# ADG714_DAC_MUX.net
KiCad netlist of a schematic drawn in Altium Designer
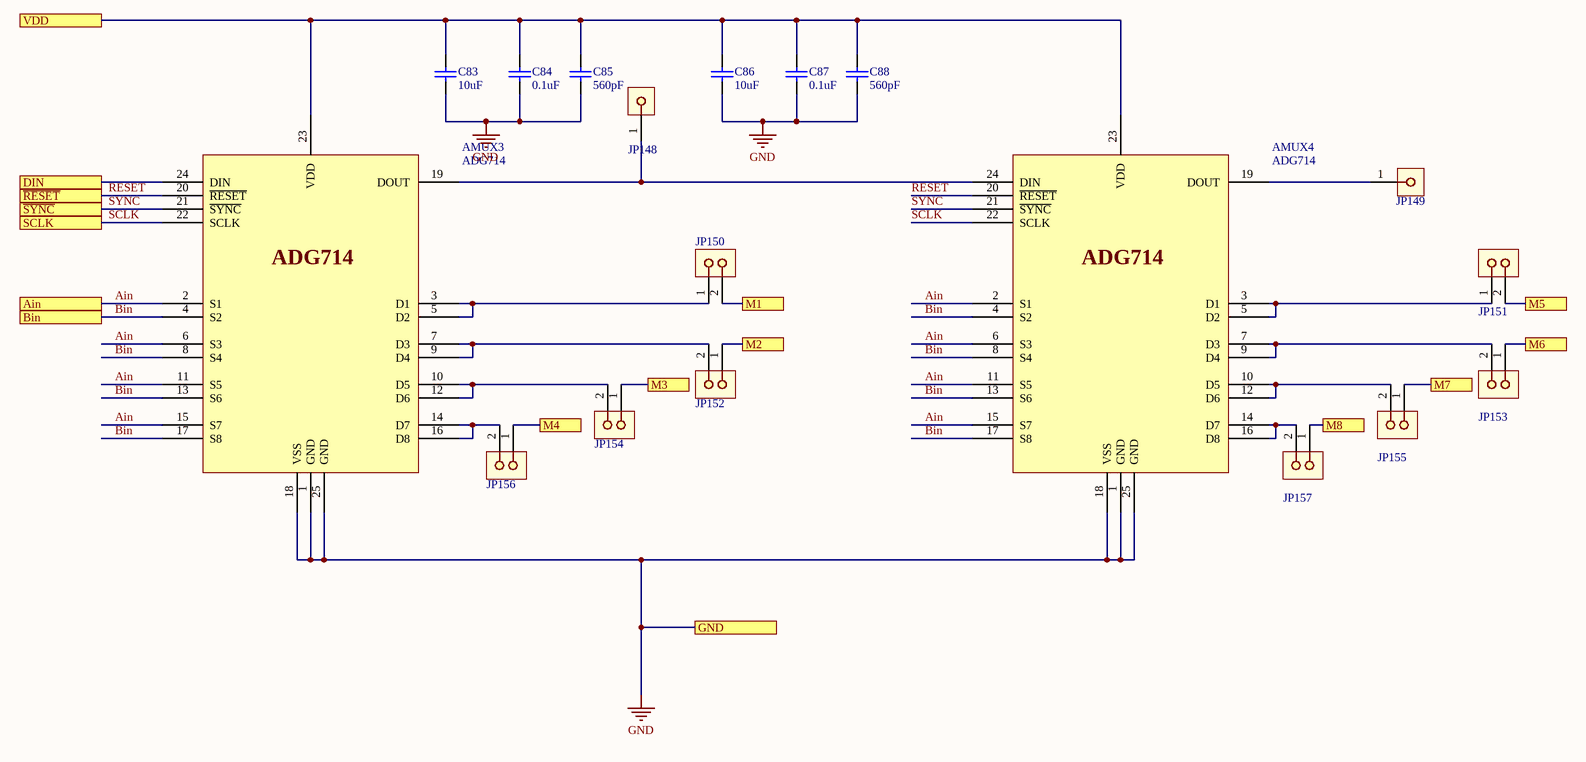
[diagram p0: ADG714_DAC_MUX.SchDoc]

(export (version "E")
  (design (tool "Eeschema 10.0.6"))
  (components
    (comp (ref "AMUX3")
      (value "ADG714")
      (footprint "ADG714BCPZ")
      (description "Analog MUX")
      (libsource (lib "Chip1_TestBoard") (part "ADG714"))
    )
    (comp (ref "AMUX4")
      (value "ADG714")
      (footprint "ADG714BCPZ")
      (description "Analog MUX")
      (libsource (lib "Chip1_TestBoard") (part "ADG714"))
    )
    (comp (ref "C83")
      (value "10uF")
      (footprint "CLS_Library:C0805")
      (description "Cap 10uF")
      (fields
        (field (name "MANUFACTURER") "Taiyo Yuden")
        (field (name "MANUFACTURER PART NUMBER") "UMK212SD103KD-T")
      )
      (libsource (lib "Chip1_TestBoard") (part "Cap 10uF"))
    )
    (comp (ref "C84")
      (value "0.1uF")
      (footprint "CLS_Library:C0805")
      (description "Cap 0.1uF")
      (fields
        (field (name "MANUFACTURER") "Taiyo Yuden")
        (field (name "MANUFACTURER PART NUMBER") "UMK212SD103KD-T")
      )
      (libsource (lib "Chip1_TestBoard") (part "Cap 0.1uF"))
    )
    (comp (ref "C85")
      (value "560pF")
      (footprint "CLS_Library:C0805")
      (description "Cap 560pF")
      (fields
        (field (name "MANUFACTURER") "Taiyo Yuden")
        (field (name "MANUFACTURER PART NUMBER") "UMK212SD103KD-T")
      )
      (libsource (lib "Chip1_TestBoard") (part "Cap 560pF"))
    )
    (comp (ref "C86")
      (value "10uF")
      (footprint "CLS_Library:C0805")
      (description "Cap 10uF")
      (fields
        (field (name "MANUFACTURER") "Taiyo Yuden")
        (field (name "MANUFACTURER PART NUMBER") "UMK212SD103KD-T")
      )
      (libsource (lib "Chip1_TestBoard") (part "Cap 10uF"))
    )
    (comp (ref "C87")
      (value "0.1uF")
      (footprint "CLS_Library:C0805")
      (description "Cap 0.1uF")
      (fields
        (field (name "MANUFACTURER") "Taiyo Yuden")
        (field (name "MANUFACTURER PART NUMBER") "UMK212SD103KD-T")
      )
      (libsource (lib "Chip1_TestBoard") (part "Cap 0.1uF"))
    )
    (comp (ref "C88")
      (value "560pF")
      (footprint "CLS_Library:C0805")
      (description "Cap 560pF")
      (fields
        (field (name "MANUFACTURER") "Taiyo Yuden")
        (field (name "MANUFACTURER PART NUMBER") "UMK212SD103KD-T")
      )
      (libsource (lib "Chip1_TestBoard") (part "Cap 560pF"))
    )
    (comp (ref "JP148")
      (value "01x01")
      (footprint "01x01_0_0.1in_th_straight_b_nom")
      (description "01X01 generic terminal connector")
      (libsource (lib "") (part "01x01_1"))
    )
    (comp (ref "JP149")
      (value "01x01")
      (footprint "01x01_0_0.1in_th_straight_b_nom")
      (description "01X01 generic terminal connector")
      (libsource (lib "Chip1_TestBoard") (part "01x01"))
    )
    (comp (ref "JP150")
      (value "01x02")
      (footprint "01x02_0.1in_th_straight_b_nom")
      (description "01X02 generic terminal connector")
      (libsource (lib "Chip1_TestBoard") (part "01x02"))
    )
    (comp (ref "JP151")
      (value "01x02")
      (footprint "01x02_0.1in_th_straight_b_nom")
      (description "01X02 generic terminal connector")
      (libsource (lib "Chip1_TestBoard") (part "01x02"))
    )
    (comp (ref "JP152")
      (value "01x02")
      (footprint "01x02_0.1in_th_straight_b_nom")
      (description "01X02 generic terminal connector")
      (libsource (lib "") (part "01x02_1"))
    )
    (comp (ref "JP153")
      (value "01x02")
      (footprint "01x02_0.1in_th_straight_b_nom")
      (description "01X02 generic terminal connector")
      (libsource (lib "") (part "01x02_1"))
    )
    (comp (ref "JP154")
      (value "01x02")
      (footprint "01x02_0.1in_th_straight_b_nom")
      (description "01X02 generic terminal connector")
      (libsource (lib "") (part "01x02_1"))
    )
    (comp (ref "JP155")
      (value "01x02")
      (footprint "01x02_0.1in_th_straight_b_nom")
      (description "01X02 generic terminal connector")
      (libsource (lib "") (part "01x02_1"))
    )
    (comp (ref "JP156")
      (value "01x02")
      (footprint "01x02_0.1in_th_straight_b_nom")
      (description "01X02 generic terminal connector")
      (libsource (lib "") (part "01x02_1"))
    )
    (comp (ref "JP157")
      (value "01x02")
      (footprint "01x02_0.1in_th_straight_b_nom")
      (description "01X02 generic terminal connector")
      (libsource (lib "") (part "01x02_1"))
    )
  )
  (nets
    (net (code "1") (name "/Ain") (class "Default")
      (node (ref "AMUX3") (pin "11") (pinfunction "S5_11") (pintype "passive"))
      (node (ref "AMUX3") (pin "15") (pinfunction "S7_15") (pintype "passive"))
      (node (ref "AMUX3") (pin "2") (pinfunction "S1_2") (pintype "passive"))
      (node (ref "AMUX3") (pin "6") (pinfunction "S3_6") (pintype "passive"))
      (node (ref "AMUX4") (pin "11") (pinfunction "S5_11") (pintype "passive"))
      (node (ref "AMUX4") (pin "15") (pinfunction "S7_15") (pintype "passive"))
      (node (ref "AMUX4") (pin "2") (pinfunction "S1_2") (pintype "passive"))
      (node (ref "AMUX4") (pin "6") (pinfunction "S3_6") (pintype "passive"))
    )
    (net (code "2") (name "/Bin") (class "Default")
      (node (ref "AMUX3") (pin "13") (pinfunction "S6_13") (pintype "passive"))
      (node (ref "AMUX3") (pin "17") (pinfunction "S8_17") (pintype "passive"))
      (node (ref "AMUX3") (pin "4") (pinfunction "S2_4") (pintype "passive"))
      (node (ref "AMUX3") (pin "8") (pinfunction "S4_8") (pintype "passive"))
      (node (ref "AMUX4") (pin "13") (pinfunction "S6_13") (pintype "passive"))
      (node (ref "AMUX4") (pin "17") (pinfunction "S8_17") (pintype "passive"))
      (node (ref "AMUX4") (pin "4") (pinfunction "S2_4") (pintype "passive"))
      (node (ref "AMUX4") (pin "8") (pinfunction "S4_8") (pintype "passive"))
    )
    (net (code "3") (name "/DIN") (class "Default")
      (node (ref "AMUX3") (pin "24") (pinfunction "DIN_24") (pintype "passive"))
    )
    (net (code "4") (name "/M1") (class "Default")
      (node (ref "JP150") (pin "2") (pinfunction "2_2") (pintype "passive"))
    )
    (net (code "5") (name "/M2") (class "Default")
      (node (ref "JP152") (pin "1") (pinfunction "1_1") (pintype "passive"))
    )
    (net (code "6") (name "/M3") (class "Default")
      (node (ref "JP154") (pin "1") (pinfunction "1_1") (pintype "passive"))
    )
    (net (code "7") (name "/M4") (class "Default")
      (node (ref "JP156") (pin "1") (pinfunction "1_1") (pintype "passive"))
    )
    (net (code "8") (name "/M5") (class "Default")
      (node (ref "JP151") (pin "2") (pinfunction "2_2") (pintype "passive"))
    )
    (net (code "9") (name "/M6") (class "Default")
      (node (ref "JP153") (pin "1") (pinfunction "1_1") (pintype "passive"))
    )
    (net (code "10") (name "/M7") (class "Default")
      (node (ref "JP155") (pin "1") (pinfunction "1_1") (pintype "passive"))
    )
    (net (code "11") (name "/M8") (class "Default")
      (node (ref "JP157") (pin "1") (pinfunction "1_1") (pintype "passive"))
    )
    (net (code "12") (name "/SCLK") (class "Default")
      (node (ref "AMUX3") (pin "22") (pinfunction "SCLK_22") (pintype "passive"))
      (node (ref "AMUX4") (pin "22") (pinfunction "SCLK_22") (pintype "passive"))
    )
    (net (code "13") (name "/VDD") (class "Default")
      (node (ref "AMUX3") (pin "23") (pinfunction "VDD_23") (pintype "passive"))
      (node (ref "AMUX4") (pin "23") (pinfunction "VDD_23") (pintype "passive"))
      (node (ref "C83") (pin "2") (pinfunction "2_2") (pintype "passive"))
      (node (ref "C84") (pin "2") (pinfunction "2_2") (pintype "passive"))
      (node (ref "C85") (pin "2") (pinfunction "2_2") (pintype "passive"))
      (node (ref "C86") (pin "2") (pinfunction "2_2") (pintype "passive"))
      (node (ref "C87") (pin "2") (pinfunction "2_2") (pintype "passive"))
      (node (ref "C88") (pin "2") (pinfunction "2_2") (pintype "passive"))
    )
    (net (code "14") (name "/~{RESET}") (class "Default")
      (node (ref "AMUX3") (pin "20") (pinfunction "~{RESET}_20") (pintype "passive"))
      (node (ref "AMUX4") (pin "20") (pinfunction "~{RESET}_20") (pintype "passive"))
    )
    (net (code "15") (name "/~{SYNC}") (class "Default")
      (node (ref "AMUX3") (pin "21") (pinfunction "~{SYNC}_21") (pintype "passive"))
      (node (ref "AMUX4") (pin "21") (pinfunction "~{SYNC}_21") (pintype "passive"))
    )
    (net (code "16") (name "GND") (class "Default")
      (node (ref "AMUX3") (pin "1") (pinfunction "GND_1") (pintype "passive"))
      (node (ref "AMUX3") (pin "18") (pinfunction "VSS_18") (pintype "passive"))
      (node (ref "AMUX3") (pin "25") (pinfunction "GND_25") (pintype "passive"))
      (node (ref "AMUX4") (pin "1") (pinfunction "GND_1") (pintype "passive"))
      (node (ref "AMUX4") (pin "18") (pinfunction "VSS_18") (pintype "passive"))
      (node (ref "AMUX4") (pin "25") (pinfunction "GND_25") (pintype "passive"))
      (node (ref "C83") (pin "1") (pinfunction "1_1") (pintype "passive"))
      (node (ref "C84") (pin "1") (pinfunction "1_1") (pintype "passive"))
      (node (ref "C85") (pin "1") (pinfunction "1_1") (pintype "passive"))
      (node (ref "C86") (pin "1") (pinfunction "1_1") (pintype "passive"))
      (node (ref "C87") (pin "1") (pinfunction "1_1") (pintype "passive"))
      (node (ref "C88") (pin "1") (pinfunction "1_1") (pintype "passive"))
    )
    (net (code "17") (name "Net-(AMUX3-D1)") (class "Default")
      (node (ref "AMUX3") (pin "3") (pinfunction "D1_3") (pintype "passive"))
      (node (ref "AMUX3") (pin "5") (pinfunction "D2_5") (pintype "passive"))
      (node (ref "JP150") (pin "1") (pinfunction "1_1") (pintype "passive"))
    )
    (net (code "18") (name "Net-(AMUX3-D3)") (class "Default")
      (node (ref "AMUX3") (pin "7") (pinfunction "D3_7") (pintype "passive"))
      (node (ref "AMUX3") (pin "9") (pinfunction "D4_9") (pintype "passive"))
      (node (ref "JP152") (pin "2") (pinfunction "2_2") (pintype "passive"))
    )
    (net (code "19") (name "Net-(AMUX3-D5)") (class "Default")
      (node (ref "AMUX3") (pin "10") (pinfunction "D5_10") (pintype "passive"))
      (node (ref "AMUX3") (pin "12") (pinfunction "D6_12") (pintype "passive"))
      (node (ref "JP154") (pin "2") (pinfunction "2_2") (pintype "passive"))
    )
    (net (code "20") (name "Net-(AMUX3-D7)") (class "Default")
      (node (ref "AMUX3") (pin "14") (pinfunction "D7_14") (pintype "passive"))
      (node (ref "AMUX3") (pin "16") (pinfunction "D8_16") (pintype "passive"))
      (node (ref "JP156") (pin "2") (pinfunction "2_2") (pintype "passive"))
    )
    (net (code "21") (name "Net-(AMUX3-DOUT)") (class "Default")
      (node (ref "AMUX3") (pin "19") (pinfunction "DOUT_19") (pintype "passive"))
      (node (ref "AMUX4") (pin "24") (pinfunction "DIN_24") (pintype "passive"))
      (node (ref "JP148") (pin "1") (pinfunction "1_1") (pintype "passive"))
    )
    (net (code "22") (name "Net-(AMUX4-D1)") (class "Default")
      (node (ref "AMUX4") (pin "3") (pinfunction "D1_3") (pintype "passive"))
      (node (ref "AMUX4") (pin "5") (pinfunction "D2_5") (pintype "passive"))
      (node (ref "JP151") (pin "1") (pinfunction "1_1") (pintype "passive"))
    )
    (net (code "23") (name "Net-(AMUX4-D3)") (class "Default")
      (node (ref "AMUX4") (pin "7") (pinfunction "D3_7") (pintype "passive"))
      (node (ref "AMUX4") (pin "9") (pinfunction "D4_9") (pintype "passive"))
      (node (ref "JP153") (pin "2") (pinfunction "2_2") (pintype "passive"))
    )
    (net (code "24") (name "Net-(AMUX4-D5)") (class "Default")
      (node (ref "AMUX4") (pin "10") (pinfunction "D5_10") (pintype "passive"))
      (node (ref "AMUX4") (pin "12") (pinfunction "D6_12") (pintype "passive"))
      (node (ref "JP155") (pin "2") (pinfunction "2_2") (pintype "passive"))
    )
    (net (code "25") (name "Net-(AMUX4-D7)") (class "Default")
      (node (ref "AMUX4") (pin "14") (pinfunction "D7_14") (pintype "passive"))
      (node (ref "AMUX4") (pin "16") (pinfunction "D8_16") (pintype "passive"))
      (node (ref "JP157") (pin "2") (pinfunction "2_2") (pintype "passive"))
    )
    (net (code "26") (name "Net-(AMUX4-DOUT)") (class "Default")
      (node (ref "AMUX4") (pin "19") (pinfunction "DOUT_19") (pintype "passive"))
      (node (ref "JP149") (pin "1") (pinfunction "1_1") (pintype "passive"))
    )
  )
)
